# addon.net
KiCad netlist of a schematic drawn in EAGLE
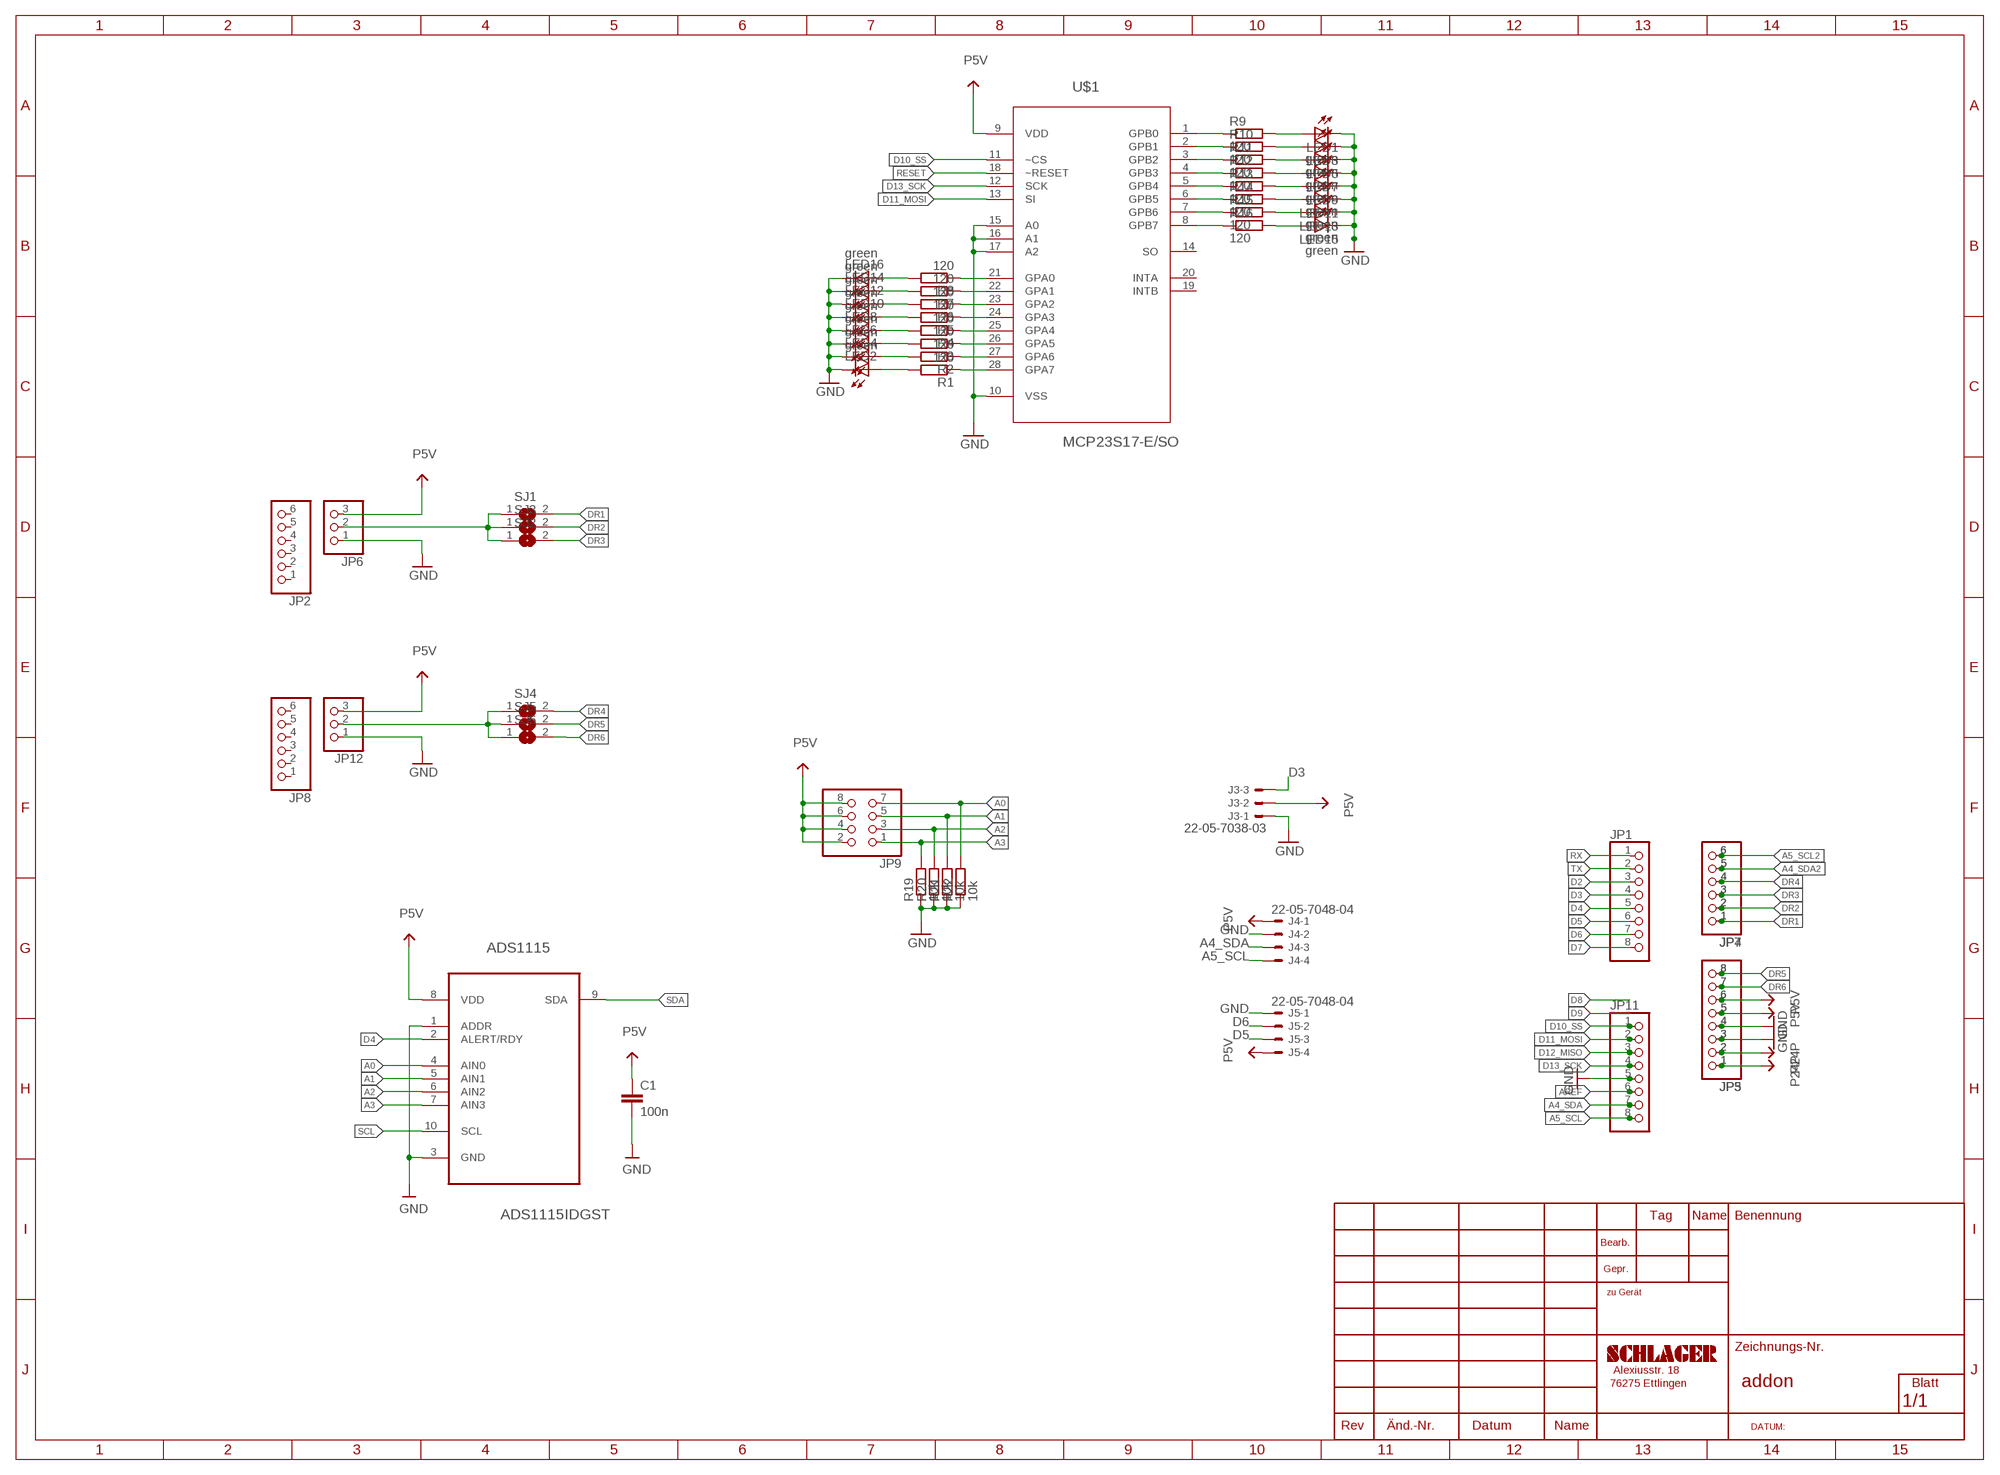
[diagram p0: schematic, sheet 1]

(export (version "E")
  (design (tool "Eeschema 10.0.6"))
  (components
    (comp (ref "ADS1115")
      (value "ADS1115IDGST")
      (footprint "eagle-import:SOP50P490X110-10N")
      (libsource (lib "eagle-import") (part "ADS1115IDGST"))
    )
    (comp (ref "C1")
      (value "100n")
      (footprint "eagle-import:C0805")
      (libsource (lib "eagle-import") (part "C-EUC0805"))
    )
    (comp (ref "J3")
      (value "22-05-7038-03")
      (footprint "eagle-import:7395-03")
      (libsource (lib "eagle-import") (part "22-?-0305-7038"))
    )
    (comp (ref "J4")
      (value "22-05-7048-04")
      (footprint "eagle-import:7395-04")
      (libsource (lib "eagle-import") (part "22-?-0405-7048"))
    )
    (comp (ref "J5")
      (value "22-05-7048-04")
      (footprint "eagle-import:7395-04")
      (libsource (lib "eagle-import") (part "22-?-0405-7048"))
    )
    (comp (ref "JP1")
      (value "PINHD-1X8")
      (footprint "eagle-import:1X08")
      (libsource (lib "eagle-import") (part "PINHD-1X8"))
    )
    (comp (ref "JP2")
      (value "PINHD-1X6")
      (footprint "eagle-import:1X06")
      (libsource (lib "eagle-import") (part "PINHD-1X6"))
    )
    (comp (ref "JP3")
      (value "PINHD-1X8")
      (footprint "eagle-import:1X08")
      (libsource (lib "eagle-import") (part "PINHD-1X8"))
    )
    (comp (ref "JP4")
      (value "PINHD-1X6")
      (footprint "eagle-import:1X06")
      (libsource (lib "eagle-import") (part "PINHD-1X6"))
    )
    (comp (ref "JP5")
      (value "PINHD-1X8")
      (footprint "eagle-import:1X08")
      (libsource (lib "eagle-import") (part "PINHD-1X8"))
    )
    (comp (ref "JP6")
      (value "PINHD-1X3")
      (footprint "eagle-import:1X03")
      (libsource (lib "eagle-import") (part "PINHD-1X3"))
    )
    (comp (ref "JP7")
      (value "PINHD-1X6")
      (footprint "eagle-import:1X06")
      (libsource (lib "eagle-import") (part "PINHD-1X6"))
    )
    (comp (ref "JP8")
      (value "PINHD-1X6")
      (footprint "eagle-import:1X06")
      (libsource (lib "eagle-import") (part "PINHD-1X6"))
    )
    (comp (ref "JP9")
      (value "PINHD-2X4/90")
      (footprint "eagle-import:2X04_90")
      (libsource (lib "eagle-import") (part "PINHD-2X4/90"))
    )
    (comp (ref "JP11")
      (value "PINHD-1X8")
      (footprint "eagle-import:1X08")
      (libsource (lib "eagle-import") (part "PINHD-1X8"))
    )
    (comp (ref "JP12")
      (value "PINHD-1X3")
      (footprint "eagle-import:1X03")
      (libsource (lib "eagle-import") (part "PINHD-1X3"))
    )
    (comp (ref "LED1")
      (value "green")
      (footprint "eagle-import:CHIPLED_0805")
      (libsource (lib "eagle-import") (part "LEDCHIPLED_0805"))
    )
    (comp (ref "LED2")
      (value "green")
      (footprint "eagle-import:CHIPLED_0805")
      (libsource (lib "eagle-import") (part "LEDCHIPLED_0805"))
    )
    (comp (ref "LED3")
      (value "green")
      (footprint "eagle-import:CHIPLED_0805")
      (libsource (lib "eagle-import") (part "LEDCHIPLED_0805"))
    )
    (comp (ref "LED4")
      (value "green")
      (footprint "eagle-import:CHIPLED_0805")
      (libsource (lib "eagle-import") (part "LEDCHIPLED_0805"))
    )
    (comp (ref "LED5")
      (value "green")
      (footprint "eagle-import:CHIPLED_0805")
      (libsource (lib "eagle-import") (part "LEDCHIPLED_0805"))
    )
    (comp (ref "LED6")
      (value "green")
      (footprint "eagle-import:CHIPLED_0805")
      (libsource (lib "eagle-import") (part "LEDCHIPLED_0805"))
    )
    (comp (ref "LED7")
      (value "green")
      (footprint "eagle-import:CHIPLED_0805")
      (libsource (lib "eagle-import") (part "LEDCHIPLED_0805"))
    )
    (comp (ref "LED8")
      (value "green")
      (footprint "eagle-import:CHIPLED_0805")
      (libsource (lib "eagle-import") (part "LEDCHIPLED_0805"))
    )
    (comp (ref "LED9")
      (value "green")
      (footprint "eagle-import:CHIPLED_0805")
      (libsource (lib "eagle-import") (part "LEDCHIPLED_0805"))
    )
    (comp (ref "LED10")
      (value "green")
      (footprint "eagle-import:CHIPLED_0805")
      (libsource (lib "eagle-import") (part "LEDCHIPLED_0805"))
    )
    (comp (ref "LED11")
      (value "green")
      (footprint "eagle-import:CHIPLED_0805")
      (libsource (lib "eagle-import") (part "LEDCHIPLED_0805"))
    )
    (comp (ref "LED12")
      (value "green")
      (footprint "eagle-import:CHIPLED_0805")
      (libsource (lib "eagle-import") (part "LEDCHIPLED_0805"))
    )
    (comp (ref "LED13")
      (value "green")
      (footprint "eagle-import:CHIPLED_0805")
      (libsource (lib "eagle-import") (part "LEDCHIPLED_0805"))
    )
    (comp (ref "LED14")
      (value "green")
      (footprint "eagle-import:CHIPLED_0805")
      (libsource (lib "eagle-import") (part "LEDCHIPLED_0805"))
    )
    (comp (ref "LED15")
      (value "green")
      (footprint "eagle-import:CHIPLED_0805")
      (libsource (lib "eagle-import") (part "LEDCHIPLED_0805"))
    )
    (comp (ref "LED16")
      (value "green")
      (footprint "eagle-import:CHIPLED_0805")
      (libsource (lib "eagle-import") (part "LEDCHIPLED_0805"))
    )
    (comp (ref "R1")
      (value "120")
      (footprint "eagle-import:R0805")
      (libsource (lib "eagle-import") (part "R-EU_R0805"))
    )
    (comp (ref "R2")
      (value "120")
      (footprint "eagle-import:R0805")
      (libsource (lib "eagle-import") (part "R-EU_R0805"))
    )
    (comp (ref "R3")
      (value "120")
      (footprint "eagle-import:R0805")
      (libsource (lib "eagle-import") (part "R-EU_R0805"))
    )
    (comp (ref "R4")
      (value "120")
      (footprint "eagle-import:R0805")
      (libsource (lib "eagle-import") (part "R-EU_R0805"))
    )
    (comp (ref "R5")
      (value "120")
      (footprint "eagle-import:R0805")
      (libsource (lib "eagle-import") (part "R-EU_R0805"))
    )
    (comp (ref "R6")
      (value "120")
      (footprint "eagle-import:R0805")
      (libsource (lib "eagle-import") (part "R-EU_R0805"))
    )
    (comp (ref "R7")
      (value "120")
      (footprint "eagle-import:R0805")
      (libsource (lib "eagle-import") (part "R-EU_R0805"))
    )
    (comp (ref "R8")
      (value "120")
      (footprint "eagle-import:R0805")
      (libsource (lib "eagle-import") (part "R-EU_R0805"))
    )
    (comp (ref "R9")
      (value "120")
      (footprint "eagle-import:R0805")
      (libsource (lib "eagle-import") (part "R-EU_R0805"))
    )
    (comp (ref "R10")
      (value "120")
      (footprint "eagle-import:R0805")
      (libsource (lib "eagle-import") (part "R-EU_R0805"))
    )
    (comp (ref "R11")
      (value "120")
      (footprint "eagle-import:R0805")
      (libsource (lib "eagle-import") (part "R-EU_R0805"))
    )
    (comp (ref "R12")
      (value "120")
      (footprint "eagle-import:R0805")
      (libsource (lib "eagle-import") (part "R-EU_R0805"))
    )
    (comp (ref "R13")
      (value "120")
      (footprint "eagle-import:R0805")
      (libsource (lib "eagle-import") (part "R-EU_R0805"))
    )
    (comp (ref "R14")
      (value "120")
      (footprint "eagle-import:R0805")
      (libsource (lib "eagle-import") (part "R-EU_R0805"))
    )
    (comp (ref "R15")
      (value "120")
      (footprint "eagle-import:R0805")
      (libsource (lib "eagle-import") (part "R-EU_R0805"))
    )
    (comp (ref "R16")
      (value "120")
      (footprint "eagle-import:R0805")
      (libsource (lib "eagle-import") (part "R-EU_R0805"))
    )
    (comp (ref "R19")
      (value "10k")
      (footprint "eagle-import:R0805")
      (libsource (lib "eagle-import") (part "R-EU_R0805"))
    )
    (comp (ref "R20")
      (value "10k")
      (footprint "eagle-import:R0805")
      (libsource (lib "eagle-import") (part "R-EU_R0805"))
    )
    (comp (ref "R21")
      (value "10k")
      (footprint "eagle-import:R0805")
      (libsource (lib "eagle-import") (part "R-EU_R0805"))
    )
    (comp (ref "R22")
      (value "10k")
      (footprint "eagle-import:R0805")
      (libsource (lib "eagle-import") (part "R-EU_R0805"))
    )
    (comp (ref "SJ1") (value "SJ") (footprint "eagle-import:SJ") (libsource (lib "eagle-import") (part "SJ")))
    (comp (ref "SJ2") (value "SJ") (footprint "eagle-import:SJ") (libsource (lib "eagle-import") (part "SJ")))
    (comp (ref "SJ3") (value "SJ") (footprint "eagle-import:SJ") (libsource (lib "eagle-import") (part "SJ")))
    (comp (ref "SJ4") (value "SJ") (footprint "eagle-import:SJ") (libsource (lib "eagle-import") (part "SJ")))
    (comp (ref "SJ5") (value "SJ") (footprint "eagle-import:SJ") (libsource (lib "eagle-import") (part "SJ")))
    (comp (ref "SJ6") (value "SJ") (footprint "eagle-import:SJ") (libsource (lib "eagle-import") (part "SJ")))
    (comp (ref "U$1")
      (value "MCP23S17-E/SO")
      (footprint "eagle-import:SOIC127P030X265-28N")
      (libsource (lib "eagle-import") (part "MCP23S17-E/SO"))
    )
  )
  (nets
    (net (code "1") (name "A0") (class "Default")
      (node (ref "ADS1115") (pin "4") (pinfunction "AIN0_4") (pintype "input"))
      (node (ref "JP9") (pin "7") (pinfunction "7_7") (pintype "passive"))
      (node (ref "R22") (pin "2") (pinfunction "2_2") (pintype "passive"))
    )
    (net (code "2") (name "A1") (class "Default")
      (node (ref "ADS1115") (pin "5") (pinfunction "AIN1_5") (pintype "input"))
      (node (ref "JP9") (pin "5") (pinfunction "5_5") (pintype "passive"))
      (node (ref "R21") (pin "2") (pinfunction "2_2") (pintype "passive"))
    )
    (net (code "3") (name "A2") (class "Default")
      (node (ref "ADS1115") (pin "6") (pinfunction "AIN2_6") (pintype "input"))
      (node (ref "JP9") (pin "3") (pinfunction "3_3") (pintype "passive"))
      (node (ref "R20") (pin "2") (pinfunction "2_2") (pintype "passive"))
    )
    (net (code "4") (name "A3") (class "Default")
      (node (ref "ADS1115") (pin "7") (pinfunction "AIN3_7") (pintype "input"))
      (node (ref "JP9") (pin "1") (pinfunction "1_1") (pintype "passive"))
      (node (ref "R19") (pin "2") (pinfunction "2_2") (pintype "passive"))
    )
    (net (code "5") (name "A4_SDA") (class "Default")
      (node (ref "J4") (pin "3") (pinfunction "S_3") (pintype "passive"))
      (node (ref "JP11") (pin "7") (pinfunction "7_7") (pintype "passive"))
    )
    (net (code "6") (name "A4_SDA2") (class "Default")
      (node (ref "JP4") (pin "5") (pinfunction "5_5") (pintype "passive"))
      (node (ref "JP7") (pin "5") (pinfunction "5_5") (pintype "passive"))
    )
    (net (code "7") (name "A5_SCL") (class "Default")
      (node (ref "J4") (pin "4") (pinfunction "S_4") (pintype "passive"))
      (node (ref "JP11") (pin "8") (pinfunction "8_8") (pintype "passive"))
    )
    (net (code "8") (name "A5_SCL2") (class "Default")
      (node (ref "JP4") (pin "6") (pinfunction "6_6") (pintype "passive"))
      (node (ref "JP7") (pin "6") (pinfunction "6_6") (pintype "passive"))
    )
    (net (code "9") (name "AREF") (class "Default")
      (node (ref "JP11") (pin "6") (pinfunction "6_6") (pintype "passive"))
    )
    (net (code "10") (name "D2") (class "Default")
      (node (ref "JP1") (pin "3") (pinfunction "3_3") (pintype "passive"))
    )
    (net (code "11") (name "D3") (class "Default")
      (node (ref "J3") (pin "3") (pinfunction "S_3") (pintype "passive"))
      (node (ref "JP1") (pin "4") (pinfunction "4_4") (pintype "passive"))
    )
    (net (code "12") (name "D4") (class "Default")
      (node (ref "ADS1115") (pin "2") (pinfunction "ALERT/RDY_2") (pintype "input"))
      (node (ref "JP1") (pin "5") (pinfunction "5_5") (pintype "passive"))
    )
    (net (code "13") (name "D5") (class "Default")
      (node (ref "J5") (pin "3") (pinfunction "S_3") (pintype "passive"))
      (node (ref "JP1") (pin "6") (pinfunction "6_6") (pintype "passive"))
    )
    (net (code "14") (name "D6") (class "Default")
      (node (ref "J5") (pin "2") (pinfunction "S_2") (pintype "passive"))
      (node (ref "JP1") (pin "7") (pinfunction "7_7") (pintype "passive"))
    )
    (net (code "15") (name "D7") (class "Default")
      (node (ref "JP1") (pin "8") (pinfunction "8_8") (pintype "passive"))
    )
    (net (code "18") (name "D10_SS") (class "Default")
      (node (ref "JP11") (pin "1") (pinfunction "1_1") (pintype "passive"))
      (node (ref "U$1") (pin "11") (pinfunction "~{CS}_11") (pintype "input"))
    )
    (net (code "19") (name "D11_MOSI") (class "Default")
      (node (ref "JP11") (pin "2") (pinfunction "2_2") (pintype "passive"))
      (node (ref "U$1") (pin "13") (pinfunction "SI_13") (pintype "input"))
    )
    (net (code "20") (name "D12_MISO") (class "Default")
      (node (ref "JP11") (pin "3") (pinfunction "3_3") (pintype "passive"))
    )
    (net (code "21") (name "D13_SCK") (class "Default")
      (node (ref "JP11") (pin "4") (pinfunction "4_4") (pintype "passive"))
      (node (ref "U$1") (pin "12") (pinfunction "SCK_12") (pintype "input"))
    )
    (net (code "22") (name "DR1") (class "Default")
      (node (ref "JP4") (pin "1") (pinfunction "1_1") (pintype "passive"))
      (node (ref "JP7") (pin "1") (pinfunction "1_1") (pintype "passive"))
      (node (ref "SJ1") (pin "2") (pinfunction "2_2") (pintype "passive"))
    )
    (net (code "23") (name "DR2") (class "Default")
      (node (ref "JP4") (pin "2") (pinfunction "2_2") (pintype "passive"))
      (node (ref "JP7") (pin "2") (pinfunction "2_2") (pintype "passive"))
      (node (ref "SJ3") (pin "2") (pinfunction "2_2") (pintype "passive"))
    )
    (net (code "24") (name "DR3") (class "Default")
      (node (ref "JP4") (pin "3") (pinfunction "3_3") (pintype "passive"))
      (node (ref "JP7") (pin "3") (pinfunction "3_3") (pintype "passive"))
      (node (ref "SJ2") (pin "2") (pinfunction "2_2") (pintype "passive"))
    )
    (net (code "25") (name "DR4") (class "Default")
      (node (ref "JP4") (pin "4") (pinfunction "4_4") (pintype "passive"))
      (node (ref "JP7") (pin "4") (pinfunction "4_4") (pintype "passive"))
      (node (ref "SJ4") (pin "2") (pinfunction "2_2") (pintype "passive"))
    )
    (net (code "26") (name "DR5") (class "Default")
      (node (ref "JP3") (pin "8") (pinfunction "8_8") (pintype "passive"))
      (node (ref "JP5") (pin "8") (pinfunction "8_8") (pintype "passive"))
      (node (ref "SJ5") (pin "2") (pinfunction "2_2") (pintype "passive"))
    )
    (net (code "27") (name "DR6") (class "Default")
      (node (ref "JP3") (pin "7") (pinfunction "7_7") (pintype "passive"))
      (node (ref "JP5") (pin "7") (pinfunction "7_7") (pintype "passive"))
      (node (ref "SJ6") (pin "2") (pinfunction "2_2") (pintype "passive"))
    )
    (net (code "28") (name "GND") (class "Default")
      (node (ref "ADS1115") (pin "1") (pinfunction "ADDR_1") (pintype "input"))
      (node (ref "ADS1115") (pin "3") (pinfunction "GND_3") (pintype "passive"))
      (node (ref "C1") (pin "2") (pinfunction "2_2") (pintype "passive"))
      (node (ref "J3") (pin "1") (pinfunction "S_1") (pintype "passive"))
      (node (ref "J4") (pin "2") (pinfunction "S_2") (pintype "passive"))
      (node (ref "J5") (pin "1") (pinfunction "S_1") (pintype "passive"))
      (node (ref "JP11") (pin "5") (pinfunction "5_5") (pintype "passive"))
      (node (ref "JP12") (pin "1") (pinfunction "1_1") (pintype "passive"))
      (node (ref "JP3") (pin "3") (pinfunction "3_3") (pintype "passive"))
      (node (ref "JP3") (pin "4") (pinfunction "4_4") (pintype "passive"))
      (node (ref "JP5") (pin "3") (pinfunction "3_3") (pintype "passive"))
      (node (ref "JP5") (pin "4") (pinfunction "4_4") (pintype "passive"))
      (node (ref "JP6") (pin "1") (pinfunction "1_1") (pintype "passive"))
      (node (ref "LED1") (pin "C") (pinfunction "C_C") (pintype "passive"))
      (node (ref "LED10") (pin "C") (pinfunction "C_C") (pintype "passive"))
      (node (ref "LED11") (pin "C") (pinfunction "C_C") (pintype "passive"))
      (node (ref "LED12") (pin "C") (pinfunction "C_C") (pintype "passive"))
      (node (ref "LED13") (pin "C") (pinfunction "C_C") (pintype "passive"))
      (node (ref "LED14") (pin "C") (pinfunction "C_C") (pintype "passive"))
      (node (ref "LED15") (pin "C") (pinfunction "C_C") (pintype "passive"))
      (node (ref "LED16") (pin "C") (pinfunction "C_C") (pintype "passive"))
      (node (ref "LED2") (pin "C") (pinfunction "C_C") (pintype "passive"))
      (node (ref "LED3") (pin "C") (pinfunction "C_C") (pintype "passive"))
      (node (ref "LED4") (pin "C") (pinfunction "C_C") (pintype "passive"))
      (node (ref "LED5") (pin "C") (pinfunction "C_C") (pintype "passive"))
      (node (ref "LED6") (pin "C") (pinfunction "C_C") (pintype "passive"))
      (node (ref "LED7") (pin "C") (pinfunction "C_C") (pintype "passive"))
      (node (ref "LED8") (pin "C") (pinfunction "C_C") (pintype "passive"))
      (node (ref "LED9") (pin "C") (pinfunction "C_C") (pintype "passive"))
      (node (ref "R19") (pin "1") (pinfunction "1_1") (pintype "passive"))
      (node (ref "R20") (pin "1") (pinfunction "1_1") (pintype "passive"))
      (node (ref "R21") (pin "1") (pinfunction "1_1") (pintype "passive"))
      (node (ref "R22") (pin "1") (pinfunction "1_1") (pintype "passive"))
      (node (ref "U$1") (pin "10") (pinfunction "VSS_10") (pintype "power_in"))
      (node (ref "U$1") (pin "15") (pinfunction "A0_15") (pintype "input"))
      (node (ref "U$1") (pin "16") (pinfunction "A1_16") (pintype "input"))
      (node (ref "U$1") (pin "17") (pinfunction "A2_17") (pintype "input"))
    )
    (net (code "29") (name "Net-(JP6-Pad2)") (class "Default")
      (node (ref "JP6") (pin "2") (pinfunction "2_2") (pintype "passive"))
      (node (ref "SJ1") (pin "1") (pinfunction "1_1") (pintype "passive"))
      (node (ref "SJ2") (pin "1") (pinfunction "1_1") (pintype "passive"))
      (node (ref "SJ3") (pin "1") (pinfunction "1_1") (pintype "passive"))
    )
    (net (code "30") (name "Net-(JP12-Pad2)") (class "Default")
      (node (ref "JP12") (pin "2") (pinfunction "2_2") (pintype "passive"))
      (node (ref "SJ4") (pin "1") (pinfunction "1_1") (pintype "passive"))
      (node (ref "SJ5") (pin "1") (pinfunction "1_1") (pintype "passive"))
      (node (ref "SJ6") (pin "1") (pinfunction "1_1") (pintype "passive"))
    )
    (net (code "31") (name "Net-(LED1-PadA)") (class "Default")
      (node (ref "LED1") (pin "A") (pinfunction "A_A") (pintype "passive"))
      (node (ref "R9") (pin "2") (pinfunction "2_2") (pintype "passive"))
    )
    (net (code "32") (name "Net-(LED2-PadA)") (class "Default")
      (node (ref "LED2") (pin "A") (pinfunction "A_A") (pintype "passive"))
      (node (ref "R1") (pin "2") (pinfunction "2_2") (pintype "passive"))
    )
    (net (code "33") (name "Net-(LED3-PadA)") (class "Default")
      (node (ref "LED3") (pin "A") (pinfunction "A_A") (pintype "passive"))
      (node (ref "R10") (pin "2") (pinfunction "2_2") (pintype "passive"))
    )
    (net (code "34") (name "Net-(LED4-PadA)") (class "Default")
      (node (ref "LED4") (pin "A") (pinfunction "A_A") (pintype "passive"))
      (node (ref "R2") (pin "2") (pinfunction "2_2") (pintype "passive"))
    )
    (net (code "35") (name "Net-(LED5-PadA)") (class "Default")
      (node (ref "LED5") (pin "A") (pinfunction "A_A") (pintype "passive"))
      (node (ref "R11") (pin "2") (pinfunction "2_2") (pintype "passive"))
    )
    (net (code "36") (name "Net-(LED6-PadA)") (class "Default")
      (node (ref "LED6") (pin "A") (pinfunction "A_A") (pintype "passive"))
      (node (ref "R3") (pin "2") (pinfunction "2_2") (pintype "passive"))
    )
    (net (code "37") (name "Net-(LED7-PadA)") (class "Default")
      (node (ref "LED7") (pin "A") (pinfunction "A_A") (pintype "passive"))
      (node (ref "R12") (pin "2") (pinfunction "2_2") (pintype "passive"))
    )
    (net (code "38") (name "Net-(LED8-PadA)") (class "Default")
      (node (ref "LED8") (pin "A") (pinfunction "A_A") (pintype "passive"))
      (node (ref "R4") (pin "2") (pinfunction "2_2") (pintype "passive"))
    )
    (net (code "39") (name "Net-(LED9-PadA)") (class "Default")
      (node (ref "LED9") (pin "A") (pinfunction "A_A") (pintype "passive"))
      (node (ref "R13") (pin "2") (pinfunction "2_2") (pintype "passive"))
    )
    (net (code "40") (name "Net-(LED10-PadA)") (class "Default")
      (node (ref "LED10") (pin "A") (pinfunction "A_A") (pintype "passive"))
      (node (ref "R5") (pin "2") (pinfunction "2_2") (pintype "passive"))
    )
    (net (code "41") (name "Net-(LED11-PadA)") (class "Default")
      (node (ref "LED11") (pin "A") (pinfunction "A_A") (pintype "passive"))
      (node (ref "R14") (pin "2") (pinfunction "2_2") (pintype "passive"))
    )
    (net (code "42") (name "Net-(LED12-PadA)") (class "Default")
      (node (ref "LED12") (pin "A") (pinfunction "A_A") (pintype "passive"))
      (node (ref "R6") (pin "2") (pinfunction "2_2") (pintype "passive"))
    )
    (net (code "43") (name "Net-(LED13-PadA)") (class "Default")
      (node (ref "LED13") (pin "A") (pinfunction "A_A") (pintype "passive"))
      (node (ref "R15") (pin "2") (pinfunction "2_2") (pintype "passive"))
    )
    (net (code "44") (name "Net-(LED14-PadA)") (class "Default")
      (node (ref "LED14") (pin "A") (pinfunction "A_A") (pintype "passive"))
      (node (ref "R7") (pin "2") (pinfunction "2_2") (pintype "passive"))
    )
    (net (code "45") (name "Net-(LED15-PadA)") (class "Default")
      (node (ref "LED15") (pin "A") (pinfunction "A_A") (pintype "passive"))
      (node (ref "R16") (pin "2") (pinfunction "2_2") (pintype "passive"))
    )
    (net (code "46") (name "Net-(LED16-PadA)") (class "Default")
      (node (ref "LED16") (pin "A") (pinfunction "A_A") (pintype "passive"))
      (node (ref "R8") (pin "2") (pinfunction "2_2") (pintype "passive"))
    )
    (net (code "47") (name "Net-(U$1-GPA0)") (class "Default")
      (node (ref "R8") (pin "1") (pinfunction "1_1") (pintype "passive"))
      (node (ref "U$1") (pin "21") (pinfunction "GPA0_21") (pintype "bidirectional"))
    )
    (net (code "48") (name "Net-(U$1-GPA1)") (class "Default")
      (node (ref "R7") (pin "1") (pinfunction "1_1") (pintype "passive"))
      (node (ref "U$1") (pin "22") (pinfunction "GPA1_22") (pintype "bidirectional"))
    )
    (net (code "49") (name "Net-(U$1-GPA2)") (class "Default")
      (node (ref "R6") (pin "1") (pinfunction "1_1") (pintype "passive"))
      (node (ref "U$1") (pin "23") (pinfunction "GPA2_23") (pintype "bidirectional"))
    )
    (net (code "50") (name "Net-(U$1-GPA3)") (class "Default")
      (node (ref "R5") (pin "1") (pinfunction "1_1") (pintype "passive"))
      (node (ref "U$1") (pin "24") (pinfunction "GPA3_24") (pintype "bidirectional"))
    )
    (net (code "51") (name "Net-(U$1-GPA4)") (class "Default")
      (node (ref "R4") (pin "1") (pinfunction "1_1") (pintype "passive"))
      (node (ref "U$1") (pin "25") (pinfunction "GPA4_25") (pintype "bidirectional"))
    )
    (net (code "52") (name "Net-(U$1-GPA5)") (class "Default")
      (node (ref "R3") (pin "1") (pinfunction "1_1") (pintype "passive"))
      (node (ref "U$1") (pin "26") (pinfunction "GPA5_26") (pintype "bidirectional"))
    )
    (net (code "53") (name "Net-(U$1-GPA6)") (class "Default")
      (node (ref "R2") (pin "1") (pinfunction "1_1") (pintype "passive"))
      (node (ref "U$1") (pin "27") (pinfunction "GPA6_27") (pintype "bidirectional"))
    )
    (net (code "54") (name "Net-(U$1-GPA7)") (class "Default")
      (node (ref "R1") (pin "1") (pinfunction "1_1") (pintype "passive"))
      (node (ref "U$1") (pin "28") (pinfunction "GPA7_28") (pintype "bidirectional"))
    )
    (net (code "55") (name "Net-(U$1-GPB0)") (class "Default")
      (node (ref "R9") (pin "1") (pinfunction "1_1") (pintype "passive"))
      (node (ref "U$1") (pin "1") (pinfunction "GPB0_1") (pintype "bidirectional"))
    )
    (net (code "56") (name "Net-(U$1-GPB1)") (class "Default")
      (node (ref "R10") (pin "1") (pinfunction "1_1") (pintype "passive"))
      (node (ref "U$1") (pin "2") (pinfunction "GPB1_2") (pintype "bidirectional"))
    )
    (net (code "57") (name "Net-(U$1-GPB2)") (class "Default")
      (node (ref "R11") (pin "1") (pinfunction "1_1") (pintype "passive"))
      (node (ref "U$1") (pin "3") (pinfunction "GPB2_3") (pintype "bidirectional"))
    )
    (net (code "58") (name "Net-(U$1-GPB3)") (class "Default")
      (node (ref "R12") (pin "1") (pinfunction "1_1") (pintype "passive"))
      (node (ref "U$1") (pin "4") (pinfunction "GPB3_4") (pintype "bidirectional"))
    )
    (net (code "59") (name "Net-(U$1-GPB4)") (class "Default")
      (node (ref "R13") (pin "1") (pinfunction "1_1") (pintype "passive"))
      (node (ref "U$1") (pin "5") (pinfunction "GPB4_5") (pintype "bidirectional"))
    )
    (net (code "60") (name "Net-(U$1-GPB5)") (class "Default")
      (node (ref "R14") (pin "1") (pinfunction "1_1") (pintype "passive"))
      (node (ref "U$1") (pin "6") (pinfunction "GPB5_6") (pintype "bidirectional"))
    )
    (net (code "61") (name "Net-(U$1-GPB6)") (class "Default")
      (node (ref "R15") (pin "1") (pinfunction "1_1") (pintype "passive"))
      (node (ref "U$1") (pin "7") (pinfunction "GPB6_7") (pintype "bidirectional"))
    )
    (net (code "62") (name "Net-(U$1-GPB7)") (class "Default")
      (node (ref "R16") (pin "1") (pinfunction "1_1") (pintype "passive"))
      (node (ref "U$1") (pin "8") (pinfunction "GPB7_8") (pintype "bidirectional"))
    )
    (net (code "63") (name "P5V") (class "Default")
      (node (ref "ADS1115") (pin "8") (pinfunction "VDD_8") (pintype "power_in"))
      (node (ref "C1") (pin "1") (pinfunction "1_1") (pintype "passive"))
      (node (ref "J3") (pin "2") (pinfunction "S_2") (pintype "passive"))
      (node (ref "J4") (pin "1") (pinfunction "S_1") (pintype "passive"))
      (node (ref "J5") (pin "4") (pinfunction "S_4") (pintype "passive"))
      (node (ref "JP12") (pin "3") (pinfunction "3_3") (pintype "passive"))
      (node (ref "JP3") (pin "5") (pinfunction "5_5") (pintype "passive"))
      (node (ref "JP3") (pin "6") (pinfunction "6_6") (pintype "passive"))
      (node (ref "JP5") (pin "5") (pinfunction "5_5") (pintype "passive"))
      (node (ref "JP5") (pin "6") (pinfunction "6_6") (pintype "passive"))
      (node (ref "JP6") (pin "3") (pinfunction "3_3") (pintype "passive"))
      (node (ref "JP9") (pin "2") (pinfunction "2_2") (pintype "passive"))
      (node (ref "JP9") (pin "4") (pinfunction "4_4") (pintype "passive"))
      (node (ref "JP9") (pin "6") (pinfunction "6_6") (pintype "passive"))
      (node (ref "JP9") (pin "8") (pinfunction "8_8") (pintype "passive"))
      (node (ref "U$1") (pin "9") (pinfunction "VDD_9") (pintype "power_in"))
    )
    (net (code "64") (name "P24P") (class "Default")
      (node (ref "JP3") (pin "1") (pinfunction "1_1") (pintype "passive"))
      (node (ref "JP3") (pin "2") (pinfunction "2_2") (pintype "passive"))
      (node (ref "JP5") (pin "1") (pinfunction "1_1") (pintype "passive"))
      (node (ref "JP5") (pin "2") (pinfunction "2_2") (pintype "passive"))
    )
    (net (code "65") (name "RESET") (class "Default")
      (node (ref "U$1") (pin "18") (pinfunction "~{RESET}_18") (pintype "input"))
    )
    (net (code "66") (name "RX") (class "Default")
      (node (ref "JP1") (pin "1") (pinfunction "1_1") (pintype "passive"))
    )
    (net (code "67") (name "SCL") (class "Default")
      (node (ref "ADS1115") (pin "10") (pinfunction "SCL_10") (pintype "input"))
    )
    (net (code "68") (name "SDA") (class "Default")
      (node (ref "ADS1115") (pin "9") (pinfunction "SDA_9") (pintype "bidirectional"))
    )
    (net (code "69") (name "TX") (class "Default")
      (node (ref "JP1") (pin "2") (pinfunction "2_2") (pintype "passive"))
    )
    (net (code "70") (name "unconnected-(JP2-Pad1)") (class "Default")
      (node (ref "JP2") (pin "1") (pinfunction "1_1") (pintype "passive"))
    )
    (net (code "71") (name "unconnected-(JP2-Pad2)") (class "Default")
      (node (ref "JP2") (pin "2") (pinfunction "2_2") (pintype "passive"))
    )
    (net (code "72") (name "unconnected-(JP2-Pad3)") (class "Default")
      (node (ref "JP2") (pin "3") (pinfunction "3_3") (pintype "passive"))
    )
    (net (code "73") (name "unconnected-(JP2-Pad4)") (class "Default")
      (node (ref "JP2") (pin "4") (pinfunction "4_4") (pintype "passive"))
    )
    (net (code "74") (name "unconnected-(JP2-Pad5)") (class "Default")
      (node (ref "JP2") (pin "5") (pinfunction "5_5") (pintype "passive"))
    )
    (net (code "75") (name "unconnected-(JP2-Pad6)") (class "Default")
      (node (ref "JP2") (pin "6") (pinfunction "6_6") (pintype "passive"))
    )
    (net (code "76") (name "unconnected-(JP8-Pad1)") (class "Default")
      (node (ref "JP8") (pin "1") (pinfunction "1_1") (pintype "passive"))
    )
    (net (code "77") (name "unconnected-(JP8-Pad2)") (class "Default")
      (node (ref "JP8") (pin "2") (pinfunction "2_2") (pintype "passive"))
    )
    (net (code "78") (name "unconnected-(JP8-Pad3)") (class "Default")
      (node (ref "JP8") (pin "3") (pinfunction "3_3") (pintype "passive"))
    )
    (net (code "79") (name "unconnected-(JP8-Pad4)") (class "Default")
      (node (ref "JP8") (pin "4") (pinfunction "4_4") (pintype "passive"))
    )
    (net (code "80") (name "unconnected-(JP8-Pad5)") (class "Default")
      (node (ref "JP8") (pin "5") (pinfunction "5_5") (pintype "passive"))
    )
    (net (code "81") (name "unconnected-(JP8-Pad6)") (class "Default")
      (node (ref "JP8") (pin "6") (pinfunction "6_6") (pintype "passive"))
    )
    (net (code "82") (name "unconnected-(U$1-INTA-Pad20)") (class "Default")
      (node (ref "U$1") (pin "20") (pinfunction "INTA_20") (pintype "output"))
    )
    (net (code "83") (name "unconnected-(U$1-INTB-Pad19)") (class "Default")
      (node (ref "U$1") (pin "19") (pinfunction "INTB_19") (pintype "output"))
    )
    (net (code "84") (name "unconnected-(U$1-SO-Pad14)") (class "Default")
      (node (ref "U$1") (pin "14") (pinfunction "SO_14") (pintype "output"))
    )
  )
)
